# 33_USB_VoCore.net
KiCad netlist of a schematic drawn in Altium Designer
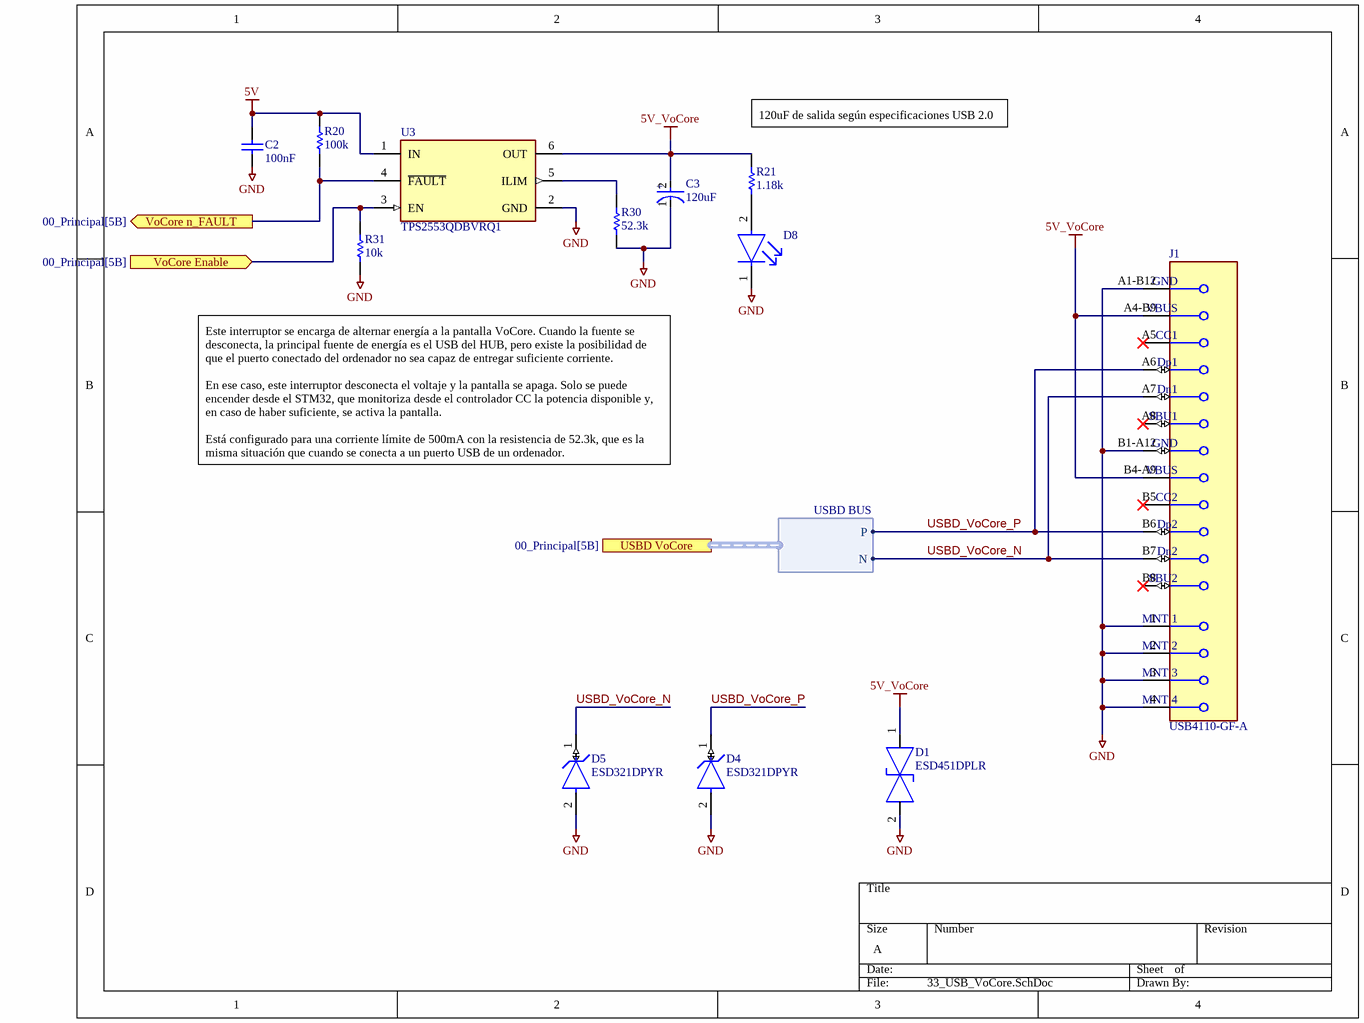
[diagram p0: 33_USB_VoCore.SchDoc]

(export (version "E")
  (design (tool "Eeschema 10.0.6"))
  (components
    (comp (ref "C2")
      (value "100nF")
      (footprint "CAPC1005X55X25NL05T05")
      (fields (field (name "MANUFACTURER") "Vitramon") (field (name "PART NUMBER") "VJ0402Y104KXJCW1BC"))
      (libsource (lib "Altium Content Vault") (part "CAP"))
    )
    (comp (ref "C3")
      (value "120uF")
      (footprint "FP-OS-CON-SMT-E7-MFG")
      (description "Conductive Polymer Aluminum Solid Capacitors (OS-CON) 120uF ±20% 10V RADIAL SMT 8x6.9mm")
      (fields (field (name "TOLERANCE") "20%") (field (name "VOLTAGE") "10V"))
      (libsource (lib "Altium Content Vault") (part "cf48714ba7e38822c1575c7ec0b6d1f"))
    )
    (comp (ref "D1")
      (value "ESD451DPLR")
      (footprint "FP-DPL0002A_MFG")
      (description "0.5-pF, 5.5-V, 30-KV bidirectional ESD protection device in 0201 package 2-X2SON -40 to 125")
      (libsource (lib "Altium Content Vault") (part "ef80418522d6051962dd4b26d32e366"))
    )
    (comp (ref "D4")
      (value "ESD321DPYR")
      (footprint "FP-DPY0002A-MFG")
      (description "HDMI2.0 ESD PROTECTION")
      (fields
        (field (name "OCTOPART") "https://octopart.com/esd321dpyr-texas+instruments-94354200")
        (field (name "MANUFACTURER") "Texas Instruments")
      )
      (libsource (lib "Altium Content Vault") (part "66ee42db3b8e3650e8893baa18e0b41"))
    )
    (comp (ref "D5")
      (value "ESD321DPYR")
      (footprint "FP-DPY0002A-MFG")
      (description "HDMI2.0 ESD PROTECTION")
      (fields
        (field (name "OCTOPART") "https://octopart.com/esd321dpyr-texas+instruments-94354200")
        (field (name "MANUFACTURER") "Texas Instruments")
      )
      (libsource (lib "Altium Content Vault") (part "66ee42db3b8e3650e8893baa18e0b41"))
    )
    (comp (ref "D8")
      (value "APHD1608LZGCK")
      (footprint "FP-APHD1608LZGCK-MFG")
      (description "LED GREEN CLEAR 1608 SMD")
      (libsource (lib "Altium Content Vault") (part "8706943c75ba83719d021d2fdc84c58"))
    )
    (comp (ref "J1")
      (value "USB4110-GF-A")
      (footprint "FP-USB4110-GF-A-MFG")
      (description "CONN USB 2.0 TYPE-C R/A SMT")
      (fields
        (field (name "OCTOPART") "https://octopart.com/usb4110-gf-a-gct-103941985")
        (field (name "MANUFACTURER") "GCT")
      )
      (libsource (lib "Altium Content Vault") (part "e23f2b38bb3c3f98e683ebab9ede730"))
    )
    (comp (ref "R20")
      (value "100k")
      (footprint "RESC1005X40X25LL05T05")
      (fields (field (name "MANUFACTURER") "Panasonic") (field (name "PART NUMBER") "ERJ-2RHD1003X"))
      (libsource (lib "Altium Content Vault") (part "RES"))
    )
    (comp (ref "R21")
      (value "1.18k")
      (footprint "RESC1005X40X25NL05T05")
      (fields (field (name "PART NUMBER") "ERJ-2RKF1181X") (field (name "MANUFACTURER") "Panasonic"))
      (libsource (lib "Altium Content Vault") (part "RES"))
    )
    (comp (ref "R30")
      (value "52.3k")
      (footprint "RESC1005X40X25LL05T05")
      (fields (field (name "PART NUMBER") "ERJ-2RKF5232X") (field (name "MANUFACTURER") "Panasonic"))
      (libsource (lib "Altium Content Vault") (part "RES"))
    )
    (comp (ref "R31")
      (value "10k")
      (footprint "RESC1005X40X25ML05T05")
      (fields (field (name "MANUFACTURER") "Panasonic") (field (name "PART NUMBER") "ERJ-2RHD1002X"))
      (libsource (lib "Altium Content Vault") (part "RES"))
    )
    (comp (ref "U3")
      (value "TPS2553QDBVRQ1")
      (footprint "FP-DBV0006A-IPC_A")
      (description "IC PWR SWITCH N-CHAN 1:1 SOT23-6")
      (libsource (lib "Altium Content Vault") (part "41ea3af657868bea7529cd464df8d50"))
    )
  )
  (nets
    (net (code "3") (name "/USBD_VoCore_N") (class "Default")
      (node (ref "D5") (pin "1") (pinfunction "IO_1") (pintype "bidirectional"))
      (node (ref "J1") (pin "A7") (pinfunction "Dn1_A7") (pintype "bidirectional"))
      (node (ref "J1") (pin "B7") (pinfunction "Dn2_B7") (pintype "bidirectional"))
    )
    (net (code "4") (name "/USBD_VoCore_P") (class "Default")
      (node (ref "D4") (pin "1") (pinfunction "IO_1") (pintype "bidirectional"))
      (node (ref "J1") (pin "A6") (pinfunction "Dp1_A6") (pintype "bidirectional"))
      (node (ref "J1") (pin "B6") (pinfunction "Dp2_B6") (pintype "bidirectional"))
    )
    (net (code "5") (name "/VoCore Enable") (class "Default")
      (node (ref "R31") (pin "2") (pinfunction "2_2") (pintype "passive"))
      (node (ref "U3") (pin "3") (pinfunction "EN_3") (pintype "input"))
    )
    (net (code "6") (name "/VoCore n_FAULT") (class "Default")
      (node (ref "R20") (pin "1") (pinfunction "1_1") (pintype "passive"))
      (node (ref "U3") (pin "4") (pinfunction "~{FAULT}_4") (pintype "open_collector"))
    )
    (net (code "8") (name "5V") (class "Default")
      (node (ref "C2") (pin "2") (pinfunction "2_2") (pintype "passive"))
      (node (ref "R20") (pin "2") (pinfunction "2_2") (pintype "passive"))
      (node (ref "U3") (pin "1") (pinfunction "IN_1") (pintype "power_in"))
    )
    (net (code "9") (name "5V_VoCore") (class "Default")
      (node (ref "C3") (pin "2") (pinfunction "A_2") (pintype "passive"))
      (node (ref "D1") (pin "1") (pinfunction "1_IO_1") (pintype "passive"))
      (node (ref "J1") (pin "A4-B9") (pinfunction "VBUS_A4-B9") (pintype "power_in"))
      (node (ref "J1") (pin "B4-A9") (pinfunction "VBUS_B4-A9") (pintype "power_in"))
      (node (ref "R21") (pin "2") (pinfunction "2_2") (pintype "passive"))
      (node (ref "U3") (pin "6") (pinfunction "OUT_6") (pintype "power_in"))
    )
    (net (code "10") (name "GND") (class "Default")
      (node (ref "C2") (pin "1") (pinfunction "1_1") (pintype "passive"))
      (node (ref "C3") (pin "1") (pinfunction "C_1") (pintype "passive"))
      (node (ref "D1") (pin "2") (pinfunction "2_IO_2") (pintype "passive"))
      (node (ref "D4") (pin "2") (pinfunction "GND_2") (pintype "power_in"))
      (node (ref "D5") (pin "2") (pinfunction "GND_2") (pintype "power_in"))
      (node (ref "D8") (pin "1") (pinfunction "C_1") (pintype "passive"))
      (node (ref "J1") (pin "1") (pinfunction "MNT_1_1") (pintype "passive"))
      (node (ref "J1") (pin "2") (pinfunction "MNT_2_2") (pintype "passive"))
      (node (ref "J1") (pin "3") (pinfunction "MNT_3_3") (pintype "passive"))
      (node (ref "J1") (pin "4") (pinfunction "MNT_4_4") (pintype "passive"))
      (node (ref "J1") (pin "A1-B12") (pinfunction "GND_A1-B12") (pintype "passive"))
      (node (ref "J1") (pin "B1-A12") (pinfunction "GND_B1-A12") (pintype "bidirectional"))
      (node (ref "R30") (pin "1") (pinfunction "1_1") (pintype "passive"))
      (node (ref "R31") (pin "1") (pinfunction "1_1") (pintype "passive"))
      (node (ref "U3") (pin "2") (pinfunction "GND_2") (pintype "passive"))
    )
    (net (code "11") (name "Net-(D8-A)") (class "Default")
      (node (ref "D8") (pin "2") (pinfunction "A_2") (pintype "passive"))
      (node (ref "R21") (pin "1") (pinfunction "1_1") (pintype "passive"))
    )
    (net (code "12") (name "Net-(U3-ILIM)") (class "Default")
      (node (ref "R30") (pin "2") (pinfunction "2_2") (pintype "passive"))
      (node (ref "U3") (pin "5") (pinfunction "ILIM_5") (pintype "output"))
    )
    (net (code "13") (name "unconnected-(J1-CC1-PadA5)") (class "Default")
      (node (ref "J1") (pin "A5") (pinfunction "CC1_A5") (pintype "passive+no_connect"))
    )
    (net (code "14") (name "unconnected-(J1-CC2-PadB5)") (class "Default")
      (node (ref "J1") (pin "B5") (pinfunction "CC2_B5") (pintype "passive+no_connect"))
    )
    (net (code "15") (name "unconnected-(J1-SBU1-PadA8)") (class "Default")
      (node (ref "J1") (pin "A8") (pinfunction "SBU1_A8") (pintype "bidirectional+no_connect"))
    )
    (net (code "16") (name "unconnected-(J1-SBU2-PadB8)") (class "Default")
      (node (ref "J1") (pin "B8") (pinfunction "SBU2_B8") (pintype "bidirectional+no_connect"))
    )
  )
)
